# master.net
KiCad netlist of a schematic drawn in EAGLE
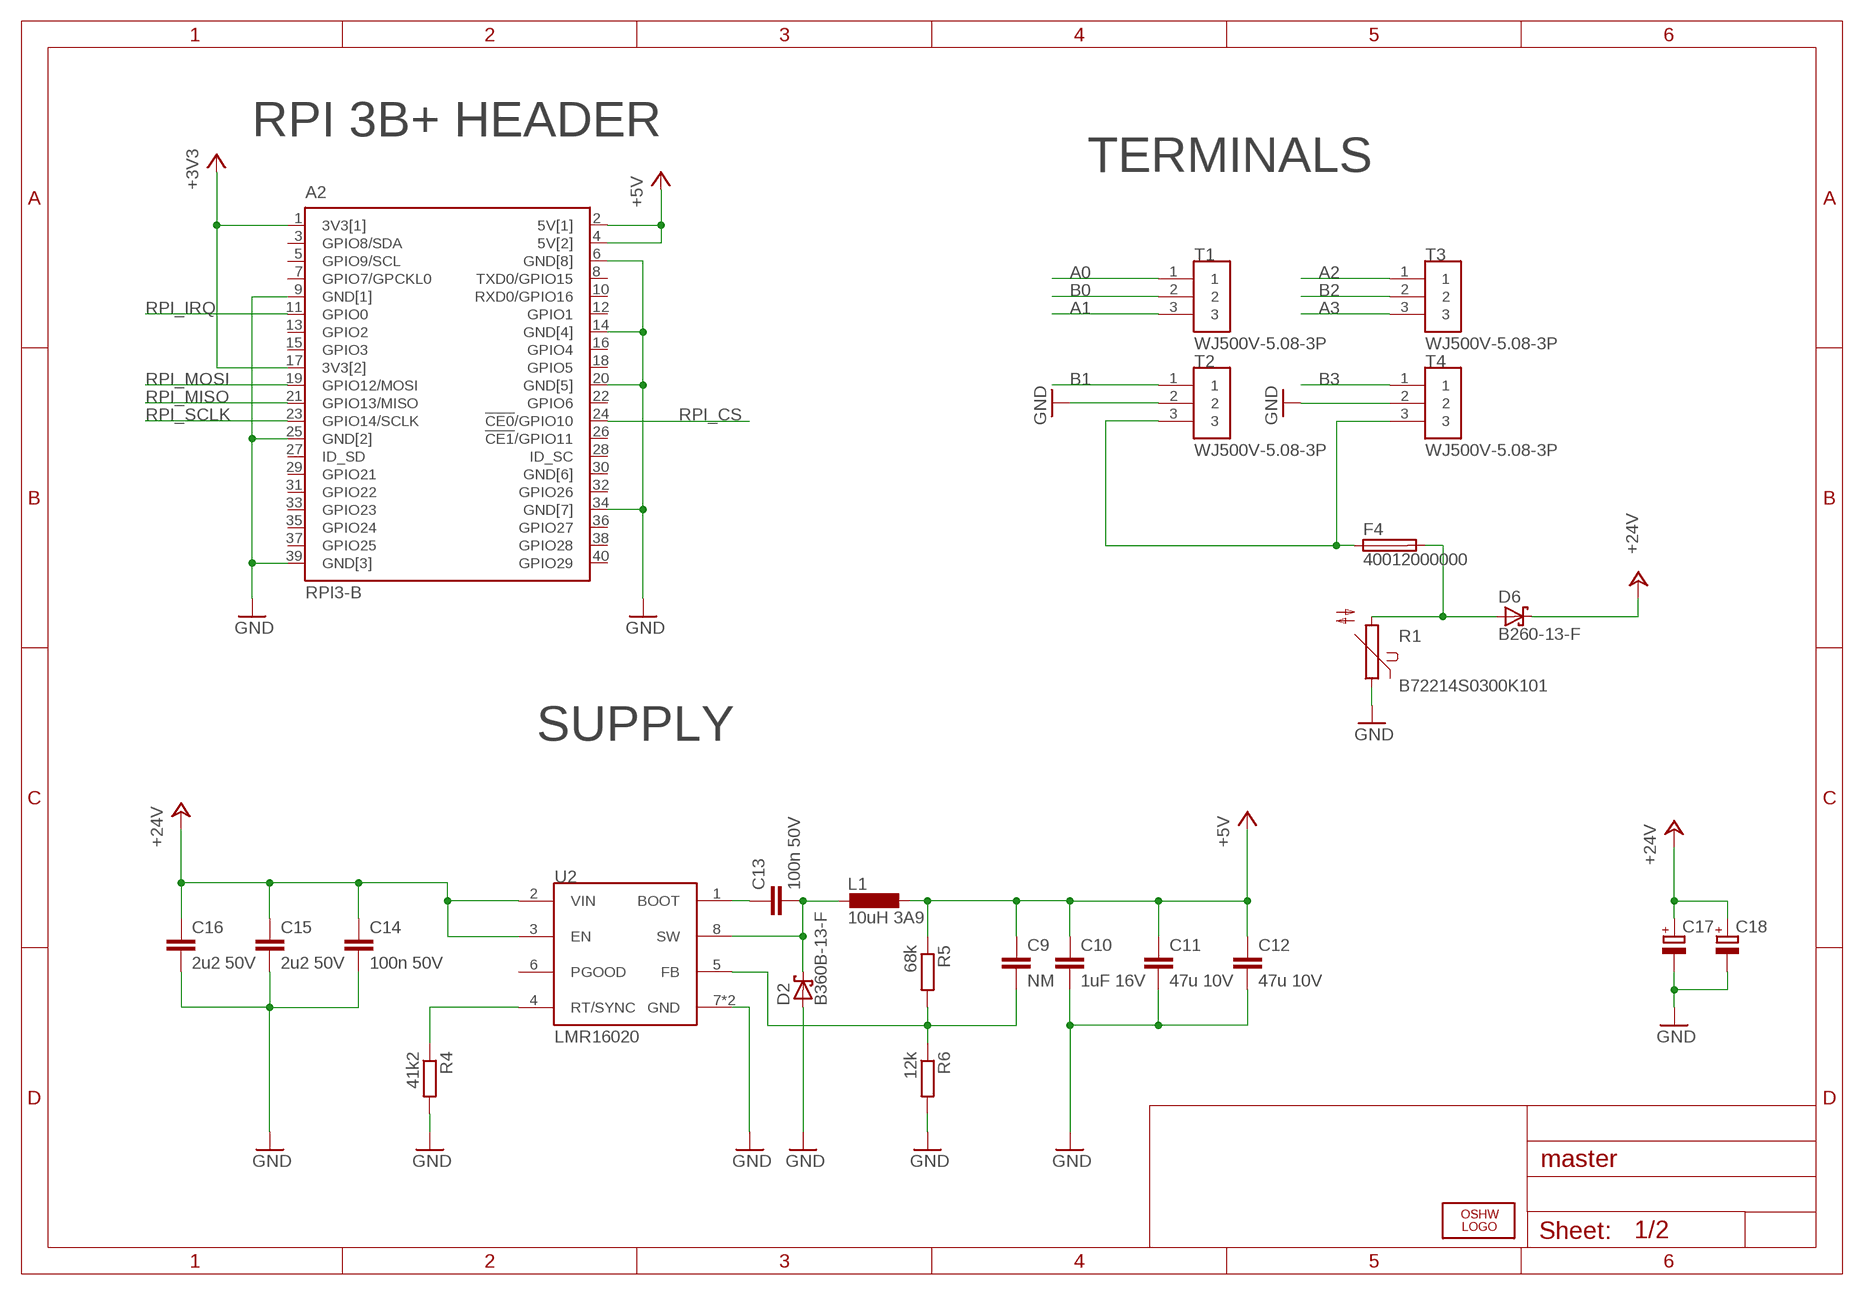
[diagram p0: schematic, sheet 1]
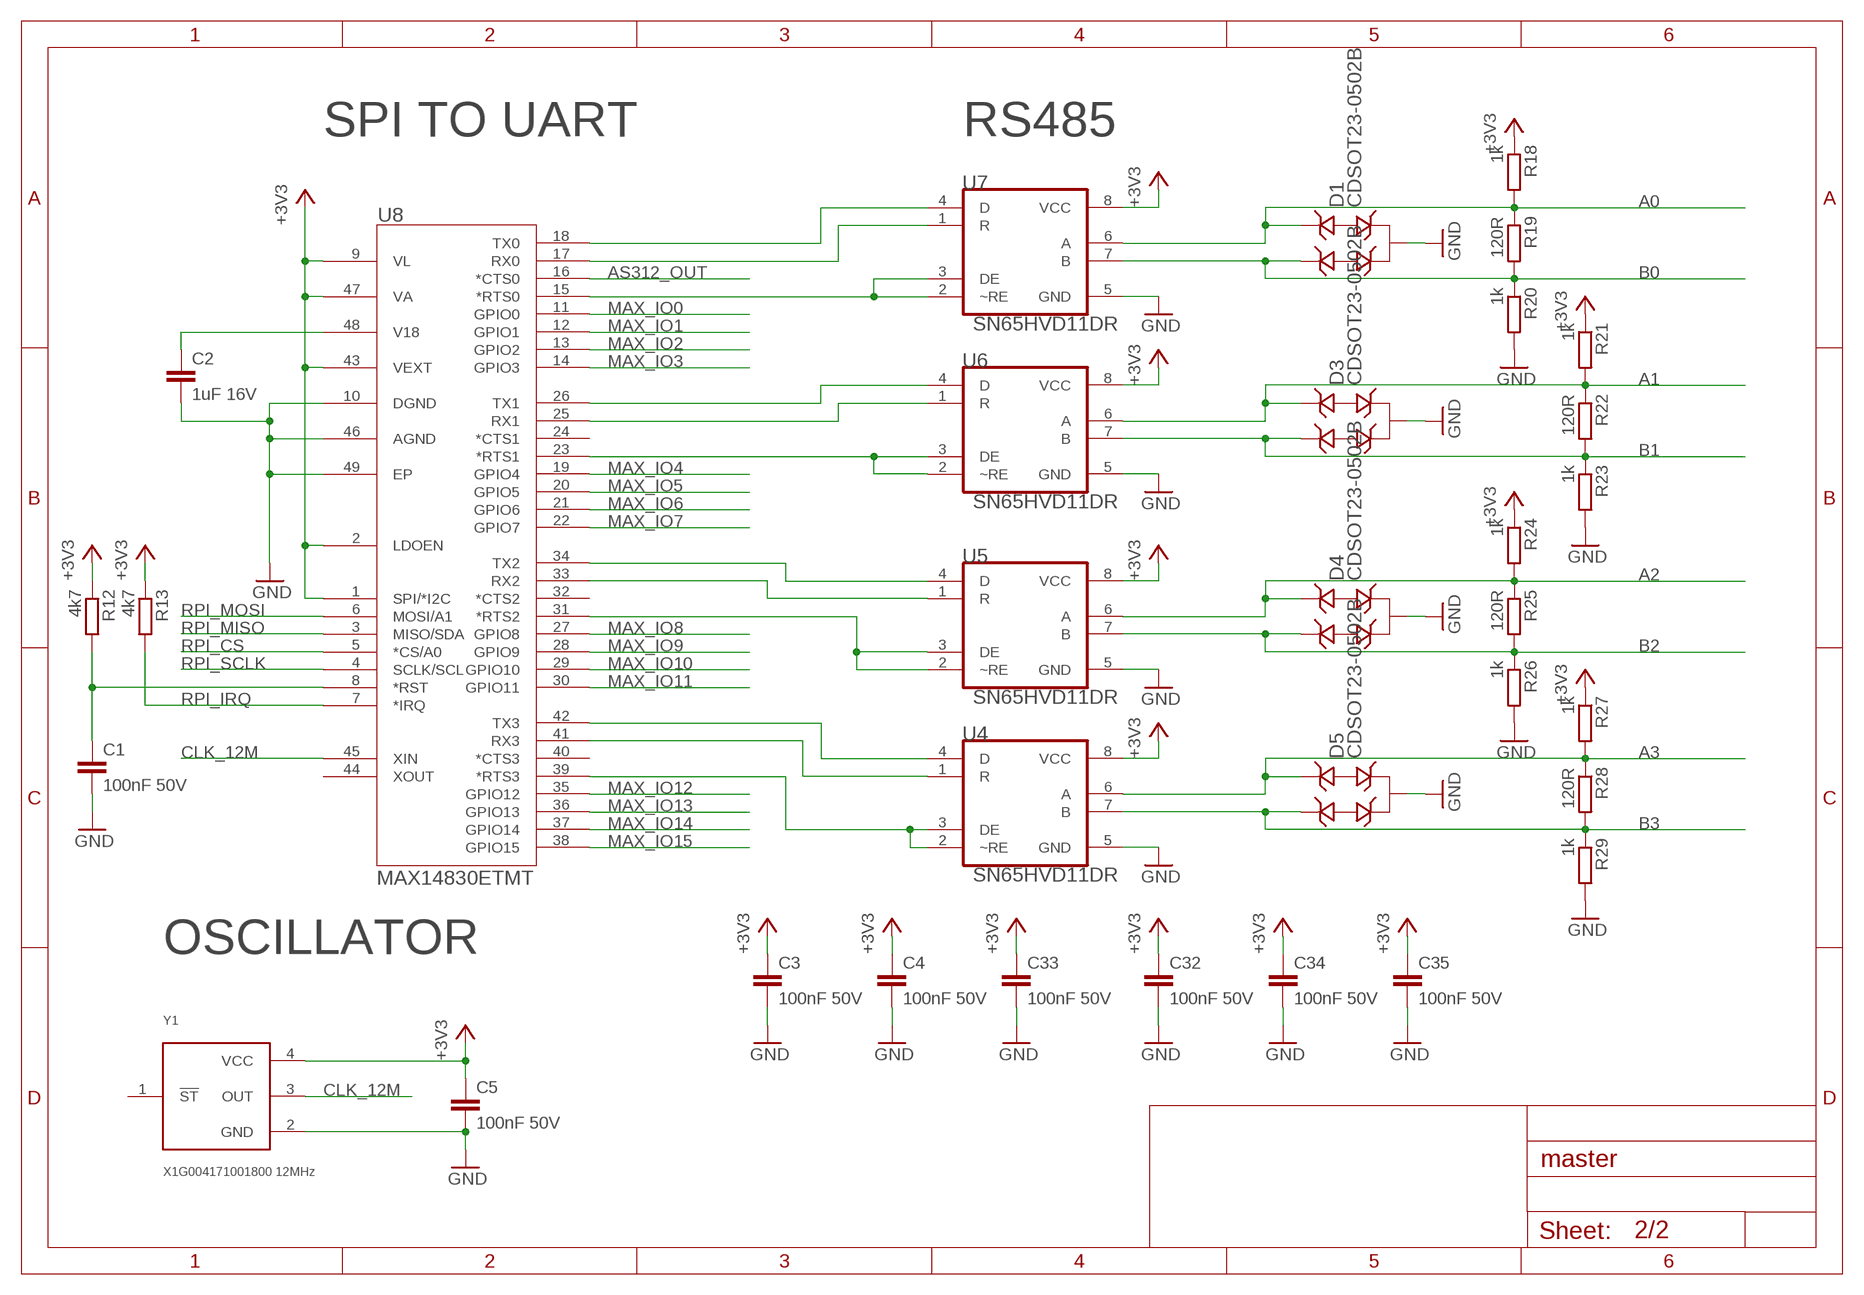
[diagram p1: schematic, sheet 2]

(export (version "E")
  (design (tool "Eeschema 10.0.6"))
  (components
    (comp (ref "C1")
      (value "100nF 50V")
      (footprint "eagle-import:C0805")
      (libsource (lib "eagle-import") (part "C-EUC0805"))
    )
    (comp (ref "C2")
      (value "1uF 16V")
      (footprint "eagle-import:C0805")
      (libsource (lib "eagle-import") (part "C-EUC0805"))
    )
    (comp (ref "C3")
      (value "100nF 50V")
      (footprint "eagle-import:C0805")
      (libsource (lib "eagle-import") (part "C-EUC0805"))
    )
    (comp (ref "C4")
      (value "100nF 50V")
      (footprint "eagle-import:C0805")
      (libsource (lib "eagle-import") (part "C-EUC0805"))
    )
    (comp (ref "C5")
      (value "100nF 50V")
      (footprint "eagle-import:C0805")
      (libsource (lib "eagle-import") (part "C-EUC0805"))
    )
    (comp (ref "C32")
      (value "100nF 50V")
      (footprint "eagle-import:C0805")
      (libsource (lib "eagle-import") (part "C-EUC0805"))
    )
    (comp (ref "C33")
      (value "100nF 50V")
      (footprint "eagle-import:C0805")
      (libsource (lib "eagle-import") (part "C-EUC0805"))
    )
    (comp (ref "C34")
      (value "100nF 50V")
      (footprint "eagle-import:C0805")
      (libsource (lib "eagle-import") (part "C-EUC0805"))
    )
    (comp (ref "C35")
      (value "100nF 50V")
      (footprint "eagle-import:C0805")
      (libsource (lib "eagle-import") (part "C-EUC0805"))
    )
    (comp (ref "D1")
      (value "CDSOT23-0502B")
      (footprint "eagle-import:SOT-23-3")
      (fields (field (name "MF") "Bourns") (field (name "MP") "CDSOT23-SM712"))
      (libsource (lib "eagle-import") (part "CDSOT23-SM712"))
    )
    (comp (ref "D3")
      (value "CDSOT23-0502B")
      (footprint "eagle-import:SOT-23-3")
      (fields (field (name "MF") "Bourns") (field (name "MP") "CDSOT23-SM712"))
      (libsource (lib "eagle-import") (part "CDSOT23-SM712"))
    )
    (comp (ref "D4")
      (value "CDSOT23-0502B")
      (footprint "eagle-import:SOT-23-3")
      (fields (field (name "MF") "Bourns") (field (name "MP") "CDSOT23-SM712"))
      (libsource (lib "eagle-import") (part "CDSOT23-SM712"))
    )
    (comp (ref "D5")
      (value "CDSOT23-0502B")
      (footprint "eagle-import:SOT-23-3")
      (fields (field (name "MF") "Bourns") (field (name "MP") "CDSOT23-SM712"))
      (libsource (lib "eagle-import") (part "CDSOT23-SM712"))
    )
    (comp (ref "R12")
      (value "4k7")
      (footprint "eagle-import:R1206")
      (libsource (lib "eagle-import") (part "R-EU_R1206"))
    )
    (comp (ref "R13")
      (value "4k7")
      (footprint "eagle-import:R1206")
      (libsource (lib "eagle-import") (part "R-EU_R1206"))
    )
    (comp (ref "R18")
      (value "1k")
      (footprint "eagle-import:R1206")
      (libsource (lib "eagle-import") (part "R-EU_R1206"))
    )
    (comp (ref "R19")
      (value "120R")
      (footprint "eagle-import:R1206")
      (libsource (lib "eagle-import") (part "R-EU_R1206"))
    )
    (comp (ref "R20")
      (value "1k")
      (footprint "eagle-import:R1206")
      (libsource (lib "eagle-import") (part "R-EU_R1206"))
    )
    (comp (ref "R21")
      (value "1k")
      (footprint "eagle-import:R1206")
      (libsource (lib "eagle-import") (part "R-EU_R1206"))
    )
    (comp (ref "R22")
      (value "120R")
      (footprint "eagle-import:R1206")
      (libsource (lib "eagle-import") (part "R-EU_R1206"))
    )
    (comp (ref "R23")
      (value "1k")
      (footprint "eagle-import:R1206")
      (libsource (lib "eagle-import") (part "R-EU_R1206"))
    )
    (comp (ref "R24")
      (value "1k")
      (footprint "eagle-import:R1206")
      (libsource (lib "eagle-import") (part "R-EU_R1206"))
    )
    (comp (ref "R25")
      (value "120R")
      (footprint "eagle-import:R1206")
      (libsource (lib "eagle-import") (part "R-EU_R1206"))
    )
    (comp (ref "R26")
      (value "1k")
      (footprint "eagle-import:R1206")
      (libsource (lib "eagle-import") (part "R-EU_R1206"))
    )
    (comp (ref "R27")
      (value "1k")
      (footprint "eagle-import:R1206")
      (libsource (lib "eagle-import") (part "R-EU_R1206"))
    )
    (comp (ref "R28")
      (value "120R")
      (footprint "eagle-import:R1206")
      (libsource (lib "eagle-import") (part "R-EU_R1206"))
    )
    (comp (ref "R29")
      (value "1k")
      (footprint "eagle-import:R1206")
      (libsource (lib "eagle-import") (part "R-EU_R1206"))
    )
    (comp (ref "U4")
      (value "SN65HVD11DR")
      (footprint "eagle-import:SOIC127P600X175-8N")
      (fields (field (name "MF") "Texas Instruments"))
      (libsource (lib "eagle-import") (part "SN65HVD11DR"))
    )
    (comp (ref "U5")
      (value "SN65HVD11DR")
      (footprint "eagle-import:SOIC127P600X175-8N")
      (fields (field (name "MF") "Texas Instruments"))
      (libsource (lib "eagle-import") (part "SN65HVD11DR"))
    )
    (comp (ref "U6")
      (value "SN65HVD11DR")
      (footprint "eagle-import:SOIC127P600X175-8N")
      (fields (field (name "MF") "Texas Instruments"))
      (libsource (lib "eagle-import") (part "SN65HVD11DR"))
    )
    (comp (ref "U7")
      (value "SN65HVD11DR")
      (footprint "eagle-import:SOIC127P600X175-8N")
      (fields (field (name "MF") "Texas Instruments"))
      (libsource (lib "eagle-import") (part "SN65HVD11DR"))
    )
    (comp (ref "U8")
      (value "MAX14830ETMT")
      (footprint "eagle-import:21-0144H_T4877-3")
      (fields (field (name "MF") "Maxim Integrated") (field (name "MP") "MAX14830ETM+"))
      (libsource (lib "eagle-import") (part "MAX14830ETMT"))
    )
    (comp (ref "Y1")
      (value "X1G004171001800 12MHz")
      (footprint "eagle-import:OSCCC250X200X80-4N")
      (fields (field (name "MF") "EPSON") (field (name "MP") "X1G0041710033"))
      (libsource (lib "eagle-import") (part "X1G0041710033"))
    )
    (comp (ref "A2")
      (value "RPI3-B")
      (footprint "eagle-import:RPI3-B")
      (fields (field (name "MF") "Raspberry Pi") (field (name "MP") "ADA3708"))
      (libsource (lib "eagle-import") (part "RPI3-B"))
    )
    (comp (ref "C9")
      (value "NM")
      (footprint "eagle-import:C0805")
      (libsource (lib "eagle-import") (part "C-EUC0805"))
    )
    (comp (ref "C10")
      (value "1uF 16V")
      (footprint "eagle-import:C0805")
      (libsource (lib "eagle-import") (part "C-EUC0805"))
    )
    (comp (ref "C11")
      (value "47u 10V")
      (footprint "eagle-import:C1210")
      (libsource (lib "eagle-import") (part "C-EUC1210"))
    )
    (comp (ref "C12")
      (value "47u 10V")
      (footprint "eagle-import:C1210")
      (libsource (lib "eagle-import") (part "C-EUC1210"))
    )
    (comp (ref "C13")
      (value "100n 50V")
      (footprint "eagle-import:C1206")
      (libsource (lib "eagle-import") (part "C-EUC1206"))
    )
    (comp (ref "C14")
      (value "100n 50V")
      (footprint "eagle-import:C1206")
      (libsource (lib "eagle-import") (part "C-EUC1206"))
    )
    (comp (ref "C15")
      (value "2u2 50V")
      (footprint "eagle-import:C1206")
      (libsource (lib "eagle-import") (part "C-EUC1206"))
    )
    (comp (ref "C16")
      (value "2u2 50V")
      (footprint "eagle-import:C1206")
      (libsource (lib "eagle-import") (part "C-EUC1206"))
    )
    (comp (ref "C17")
      (value "CPOL-EUUD-5X5,8")
      (footprint "eagle-import:UD-5X5,8_NICHICON")
      (libsource (lib "eagle-import") (part "CPOL-EUUD-5X5,8"))
    )
    (comp (ref "C18")
      (value "CPOL-EUUD-5X5,8")
      (footprint "eagle-import:UD-5X5,8_NICHICON")
      (libsource (lib "eagle-import") (part "CPOL-EUUD-5X5,8"))
    )
    (comp (ref "D2")
      (value "B360B-13-F")
      (footprint "eagle-import:SMB")
      (libsource (lib "eagle-import") (part "MBRS130LT3"))
    )
    (comp (ref "D6")
      (value "B260-13-F")
      (footprint "eagle-import:SMB")
      (libsource (lib "eagle-import") (part "MBRS130LT3"))
    )
    (comp (ref "F4")
      (value "40012000000")
      (footprint "eagle-import:400")
      (libsource (lib "eagle-import") (part "40012000000"))
    )
    (comp (ref "L1")
      (value "10uH 3A9")
      (footprint "eagle-import:1217AS")
      (libsource (lib "eagle-import") (part "1217AS-H-100M=P3"))
    )
    (comp (ref "LOGO1")
      (value "OSHW_LOGO_FILLX0350-NT")
      (footprint "eagle-import:OSHW_FILLX350_NOTEXT")
      (libsource (lib "eagle-import") (part "OSHW_LOGO_FILLX0350-NT"))
    )
    (comp (ref "R1")
      (value "B72214S0300K101")
      (footprint "eagle-import:S14K300")
      (libsource (lib "eagle-import") (part "S14K300"))
    )
    (comp (ref "R4")
      (value "41k2")
      (footprint "eagle-import:R1206")
      (libsource (lib "eagle-import") (part "R-EU_R1206"))
    )
    (comp (ref "R5")
      (value "68k")
      (footprint "eagle-import:R1206")
      (libsource (lib "eagle-import") (part "R-EU_R1206"))
    )
    (comp (ref "R6")
      (value "12k")
      (footprint "eagle-import:R1206")
      (libsource (lib "eagle-import") (part "R-EU_R1206"))
    )
    (comp (ref "T1")
      (value "WJ500V-5.08-3P")
      (footprint "eagle-import:WJ500V-5.08-3P")
      (libsource (lib "eagle-import") (part "WJ500V-5.08-3P"))
    )
    (comp (ref "T2")
      (value "WJ500V-5.08-3P")
      (footprint "eagle-import:WJ500V-5.08-3P")
      (libsource (lib "eagle-import") (part "WJ500V-5.08-3P"))
    )
    (comp (ref "T3")
      (value "WJ500V-5.08-3P")
      (footprint "eagle-import:WJ500V-5.08-3P")
      (libsource (lib "eagle-import") (part "WJ500V-5.08-3P"))
    )
    (comp (ref "T4")
      (value "WJ500V-5.08-3P")
      (footprint "eagle-import:WJ500V-5.08-3P")
      (libsource (lib "eagle-import") (part "WJ500V-5.08-3P"))
    )
    (comp (ref "U2")
      (value "LMR16020")
      (footprint "eagle-import:SOIC127P600X170-8N")
      (libsource (lib "eagle-import") (part "LMR16020"))
    )
  )
  (nets
    (net (code "1") (name "+3V3") (class "Default")
      (node (ref "A2") (pin "1") (pinfunction "3V3[1]_1") (pintype "power_in"))
      (node (ref "A2") (pin "17") (pinfunction "3V3[2]_17") (pintype "power_in"))
      (node (ref "C3") (pin "1") (pinfunction "1_1") (pintype "passive"))
      (node (ref "C32") (pin "1") (pinfunction "1_1") (pintype "passive"))
      (node (ref "C33") (pin "1") (pinfunction "1_1") (pintype "passive"))
      (node (ref "C34") (pin "1") (pinfunction "1_1") (pintype "passive"))
      (node (ref "C35") (pin "1") (pinfunction "1_1") (pintype "passive"))
      (node (ref "C4") (pin "1") (pinfunction "1_1") (pintype "passive"))
      (node (ref "C5") (pin "1") (pinfunction "1_1") (pintype "passive"))
      (node (ref "R12") (pin "1") (pinfunction "1_1") (pintype "passive"))
      (node (ref "R13") (pin "1") (pinfunction "1_1") (pintype "passive"))
      (node (ref "R18") (pin "1") (pinfunction "1_1") (pintype "passive"))
      (node (ref "R21") (pin "1") (pinfunction "1_1") (pintype "passive"))
      (node (ref "R24") (pin "1") (pinfunction "1_1") (pintype "passive"))
      (node (ref "R27") (pin "1") (pinfunction "1_1") (pintype "passive"))
      (node (ref "U4") (pin "8") (pinfunction "VCC_8") (pintype "power_in"))
      (node (ref "U5") (pin "8") (pinfunction "VCC_8") (pintype "power_in"))
      (node (ref "U6") (pin "8") (pinfunction "VCC_8") (pintype "power_in"))
      (node (ref "U7") (pin "8") (pinfunction "VCC_8") (pintype "power_in"))
      (node (ref "U8") (pin "1") (pinfunction "SPI/*I2C_1") (pintype "passive"))
      (node (ref "U8") (pin "2") (pinfunction "LDOEN_2") (pintype "passive"))
      (node (ref "U8") (pin "43") (pinfunction "VEXT_43") (pintype "passive"))
      (node (ref "U8") (pin "47") (pinfunction "VA_47") (pintype "passive"))
      (node (ref "U8") (pin "9") (pinfunction "VL_9") (pintype "power_in"))
      (node (ref "Y1") (pin "4") (pinfunction "VCC_4") (pintype "power_in"))
    )
    (net (code "2") (name "+5V") (class "Default")
      (node (ref "A2") (pin "2") (pinfunction "5V[1]_2") (pintype "power_in"))
      (node (ref "A2") (pin "4") (pinfunction "5V[2]_4") (pintype "power_in"))
      (node (ref "C10") (pin "1") (pinfunction "1_1") (pintype "passive"))
      (node (ref "C11") (pin "1") (pinfunction "1_1") (pintype "passive"))
      (node (ref "C12") (pin "1") (pinfunction "1_1") (pintype "passive"))
      (node (ref "C9") (pin "1") (pinfunction "1_1") (pintype "passive"))
      (node (ref "L1") (pin "1") (pinfunction "1_1") (pintype "passive"))
      (node (ref "R5") (pin "1") (pinfunction "1_1") (pintype "passive"))
    )
    (net (code "3") (name "+24V") (class "Default")
      (node (ref "C14") (pin "1") (pinfunction "1_1") (pintype "passive"))
      (node (ref "C15") (pin "1") (pinfunction "1_1") (pintype "passive"))
      (node (ref "C16") (pin "1") (pinfunction "1_1") (pintype "passive"))
      (node (ref "C17") (pin "+") (pinfunction "+_+") (pintype "passive"))
      (node (ref "C18") (pin "+") (pinfunction "+_+") (pintype "passive"))
      (node (ref "D6") (pin "C") (pinfunction "C_C") (pintype "passive"))
      (node (ref "U2") (pin "2") (pinfunction "VIN_2") (pintype "power_in"))
      (node (ref "U2") (pin "3") (pinfunction "EN_3") (pintype "input"))
    )
    (net (code "4") (name "A0") (class "Default")
      (node (ref "D1") (pin "2") (pinfunction "IO2_2") (pintype "bidirectional"))
      (node (ref "R18") (pin "2") (pinfunction "2_2") (pintype "passive"))
      (node (ref "R19") (pin "1") (pinfunction "1_1") (pintype "passive"))
      (node (ref "T1") (pin "1") (pinfunction "1_1") (pintype "passive"))
      (node (ref "U7") (pin "6") (pinfunction "A_6") (pintype "output"))
    )
    (net (code "5") (name "A1") (class "Default")
      (node (ref "D3") (pin "2") (pinfunction "IO2_2") (pintype "bidirectional"))
      (node (ref "R21") (pin "2") (pinfunction "2_2") (pintype "passive"))
      (node (ref "R22") (pin "1") (pinfunction "1_1") (pintype "passive"))
      (node (ref "T1") (pin "3") (pinfunction "3_3") (pintype "passive"))
      (node (ref "U6") (pin "6") (pinfunction "A_6") (pintype "output"))
    )
    (net (code "6") (name "A2") (class "Default")
      (node (ref "D4") (pin "2") (pinfunction "IO2_2") (pintype "bidirectional"))
      (node (ref "R24") (pin "2") (pinfunction "2_2") (pintype "passive"))
      (node (ref "R25") (pin "1") (pinfunction "1_1") (pintype "passive"))
      (node (ref "T3") (pin "1") (pinfunction "1_1") (pintype "passive"))
      (node (ref "U5") (pin "6") (pinfunction "A_6") (pintype "output"))
    )
    (net (code "7") (name "A3") (class "Default")
      (node (ref "D5") (pin "2") (pinfunction "IO2_2") (pintype "bidirectional"))
      (node (ref "R27") (pin "2") (pinfunction "2_2") (pintype "passive"))
      (node (ref "R28") (pin "1") (pinfunction "1_1") (pintype "passive"))
      (node (ref "T3") (pin "3") (pinfunction "3_3") (pintype "passive"))
      (node (ref "U4") (pin "6") (pinfunction "A_6") (pintype "output"))
    )
    (net (code "8") (name "AS312_OUT") (class "Default")
      (node (ref "U8") (pin "16") (pinfunction "*CTS0_16") (pintype "passive"))
    )
    (net (code "9") (name "B0") (class "Default")
      (node (ref "D1") (pin "1") (pinfunction "IO1_1") (pintype "bidirectional"))
      (node (ref "R19") (pin "2") (pinfunction "2_2") (pintype "passive"))
      (node (ref "R20") (pin "1") (pinfunction "1_1") (pintype "passive"))
      (node (ref "T1") (pin "2") (pinfunction "2_2") (pintype "passive"))
      (node (ref "U7") (pin "7") (pinfunction "B_7") (pintype "output"))
    )
    (net (code "10") (name "B1") (class "Default")
      (node (ref "D3") (pin "1") (pinfunction "IO1_1") (pintype "bidirectional"))
      (node (ref "R22") (pin "2") (pinfunction "2_2") (pintype "passive"))
      (node (ref "R23") (pin "1") (pinfunction "1_1") (pintype "passive"))
      (node (ref "T2") (pin "1") (pinfunction "1_1") (pintype "passive"))
      (node (ref "U6") (pin "7") (pinfunction "B_7") (pintype "output"))
    )
    (net (code "11") (name "B2") (class "Default")
      (node (ref "D4") (pin "1") (pinfunction "IO1_1") (pintype "bidirectional"))
      (node (ref "R25") (pin "2") (pinfunction "2_2") (pintype "passive"))
      (node (ref "R26") (pin "1") (pinfunction "1_1") (pintype "passive"))
      (node (ref "T3") (pin "2") (pinfunction "2_2") (pintype "passive"))
      (node (ref "U5") (pin "7") (pinfunction "B_7") (pintype "output"))
    )
    (net (code "12") (name "B3") (class "Default")
      (node (ref "D5") (pin "1") (pinfunction "IO1_1") (pintype "bidirectional"))
      (node (ref "R28") (pin "2") (pinfunction "2_2") (pintype "passive"))
      (node (ref "R29") (pin "1") (pinfunction "1_1") (pintype "passive"))
      (node (ref "T4") (pin "1") (pinfunction "1_1") (pintype "passive"))
      (node (ref "U4") (pin "7") (pinfunction "B_7") (pintype "output"))
    )
    (net (code "13") (name "CLK_12M") (class "Default")
      (node (ref "U8") (pin "45") (pinfunction "XIN_45") (pintype "passive"))
      (node (ref "Y1") (pin "3") (pinfunction "OUT_3") (pintype "output"))
    )
    (net (code "14") (name "GND") (class "Default")
      (node (ref "A2") (pin "14") (pinfunction "GND[4]_14") (pintype "power_in"))
      (node (ref "A2") (pin "20") (pinfunction "GND[5]_20") (pintype "power_in"))
      (node (ref "A2") (pin "25") (pinfunction "GND[2]_25") (pintype "power_in"))
      (node (ref "A2") (pin "34") (pinfunction "GND[7]_34") (pintype "power_in"))
      (node (ref "A2") (pin "39") (pinfunction "GND[3]_39") (pintype "power_in"))
      (node (ref "A2") (pin "6") (pinfunction "GND[8]_6") (pintype "power_in"))
      (node (ref "A2") (pin "9") (pinfunction "GND[1]_9") (pintype "power_in"))
      (node (ref "C1") (pin "2") (pinfunction "2_2") (pintype "passive"))
      (node (ref "C10") (pin "2") (pinfunction "2_2") (pintype "passive"))
      (node (ref "C11") (pin "2") (pinfunction "2_2") (pintype "passive"))
      (node (ref "C12") (pin "2") (pinfunction "2_2") (pintype "passive"))
      (node (ref "C14") (pin "2") (pinfunction "2_2") (pintype "passive"))
      (node (ref "C15") (pin "2") (pinfunction "2_2") (pintype "passive"))
      (node (ref "C16") (pin "2") (pinfunction "2_2") (pintype "passive"))
      (node (ref "C17") (pin "-") (pinfunction "-_-") (pintype "passive"))
      (node (ref "C18") (pin "-") (pinfunction "-_-") (pintype "passive"))
      (node (ref "C2") (pin "2") (pinfunction "2_2") (pintype "passive"))
      (node (ref "C3") (pin "2") (pinfunction "2_2") (pintype "passive"))
      (node (ref "C32") (pin "2") (pinfunction "2_2") (pintype "passive"))
      (node (ref "C33") (pin "2") (pinfunction "2_2") (pintype "passive"))
      (node (ref "C34") (pin "2") (pinfunction "2_2") (pintype "passive"))
      (node (ref "C35") (pin "2") (pinfunction "2_2") (pintype "passive"))
      (node (ref "C4") (pin "2") (pinfunction "2_2") (pintype "passive"))
      (node (ref "C5") (pin "2") (pinfunction "2_2") (pintype "passive"))
      (node (ref "D1") (pin "3") (pinfunction "GND_3") (pintype "bidirectional"))
      (node (ref "D2") (pin "A") (pinfunction "A_A") (pintype "passive"))
      (node (ref "D3") (pin "3") (pinfunction "GND_3") (pintype "bidirectional"))
      (node (ref "D4") (pin "3") (pinfunction "GND_3") (pintype "bidirectional"))
      (node (ref "D5") (pin "3") (pinfunction "GND_3") (pintype "bidirectional"))
      (node (ref "R1") (pin "1") (pinfunction "1_1") (pintype "passive"))
      (node (ref "R20") (pin "2") (pinfunction "2_2") (pintype "passive"))
      (node (ref "R23") (pin "2") (pinfunction "2_2") (pintype "passive"))
      (node (ref "R26") (pin "2") (pinfunction "2_2") (pintype "passive"))
      (node (ref "R29") (pin "2") (pinfunction "2_2") (pintype "passive"))
      (node (ref "R4") (pin "2") (pinfunction "2_2") (pintype "passive"))
      (node (ref "R6") (pin "2") (pinfunction "2_2") (pintype "passive"))
      (node (ref "T2") (pin "2") (pinfunction "2_2") (pintype "passive"))
      (node (ref "T4") (pin "2") (pinfunction "2_2") (pintype "passive"))
      (node (ref "U2") (pin "7") (pinfunction "GND_7") (pintype "power_in"))
      (node (ref "U2") (pin "9") (pinfunction "GND_9") (pintype "power_in"))
      (node (ref "U4") (pin "5") (pinfunction "GND_5") (pintype "passive"))
      (node (ref "U5") (pin "5") (pinfunction "GND_5") (pintype "passive"))
      (node (ref "U6") (pin "5") (pinfunction "GND_5") (pintype "passive"))
      (node (ref "U7") (pin "5") (pinfunction "GND_5") (pintype "passive"))
      (node (ref "U8") (pin "10") (pinfunction "DGND_10") (pintype "power_in"))
      (node (ref "U8") (pin "46") (pinfunction "AGND_46") (pintype "power_in"))
      (node (ref "U8") (pin "49") (pinfunction "EP_49") (pintype "passive"))
      (node (ref "Y1") (pin "2") (pinfunction "GND_2") (pintype "passive"))
    )
    (net (code "15") (name "GND[6]") (class "Default")
      (node (ref "A2") (pin "30") (pinfunction "GND[6]_30") (pintype "power_in"))
    )
    (net (code "16") (name "MAX_IO0") (class "Default")
      (node (ref "U8") (pin "11") (pinfunction "GPIO0_11") (pintype "passive"))
    )
    (net (code "17") (name "MAX_IO1") (class "Default")
      (node (ref "U8") (pin "12") (pinfunction "GPIO1_12") (pintype "passive"))
    )
    (net (code "18") (name "MAX_IO2") (class "Default")
      (node (ref "U8") (pin "13") (pinfunction "GPIO2_13") (pintype "passive"))
    )
    (net (code "19") (name "MAX_IO3") (class "Default")
      (node (ref "U8") (pin "14") (pinfunction "GPIO3_14") (pintype "passive"))
    )
    (net (code "20") (name "MAX_IO4") (class "Default")
      (node (ref "U8") (pin "19") (pinfunction "GPIO4_19") (pintype "passive"))
    )
    (net (code "21") (name "MAX_IO5") (class "Default")
      (node (ref "U8") (pin "20") (pinfunction "GPIO5_20") (pintype "passive"))
    )
    (net (code "22") (name "MAX_IO6") (class "Default")
      (node (ref "U8") (pin "21") (pinfunction "GPIO6_21") (pintype "passive"))
    )
    (net (code "23") (name "MAX_IO7") (class "Default")
      (node (ref "U8") (pin "22") (pinfunction "GPIO7_22") (pintype "passive"))
    )
    (net (code "24") (name "MAX_IO8") (class "Default")
      (node (ref "U8") (pin "27") (pinfunction "GPIO8_27") (pintype "passive"))
    )
    (net (code "25") (name "MAX_IO9") (class "Default")
      (node (ref "U8") (pin "28") (pinfunction "GPIO9_28") (pintype "passive"))
    )
    (net (code "26") (name "MAX_IO10") (class "Default")
      (node (ref "U8") (pin "29") (pinfunction "GPIO10_29") (pintype "passive"))
    )
    (net (code "27") (name "MAX_IO11") (class "Default")
      (node (ref "U8") (pin "30") (pinfunction "GPIO11_30") (pintype "passive"))
    )
    (net (code "28") (name "MAX_IO12") (class "Default")
      (node (ref "U8") (pin "35") (pinfunction "GPIO12_35") (pintype "passive"))
    )
    (net (code "29") (name "MAX_IO13") (class "Default")
      (node (ref "U8") (pin "36") (pinfunction "GPIO13_36") (pintype "passive"))
    )
    (net (code "30") (name "MAX_IO14") (class "Default")
      (node (ref "U8") (pin "37") (pinfunction "GPIO14_37") (pintype "passive"))
    )
    (net (code "31") (name "MAX_IO15") (class "Default")
      (node (ref "U8") (pin "38") (pinfunction "GPIO15_38") (pintype "passive"))
    )
    (net (code "32") (name "Net-(F4-1)") (class "Default")
      (node (ref "F4") (pin "P$1") (pinfunction "1_P$1") (pintype "passive"))
      (node (ref "T2") (pin "3") (pinfunction "3_3") (pintype "passive"))
      (node (ref "T4") (pin "3") (pinfunction "3_3") (pintype "passive"))
    )
    (net (code "33") (name "Net-(F4-2)") (class "Default")
      (node (ref "D6") (pin "A") (pinfunction "A_A") (pintype "passive"))
      (node (ref "F4") (pin "P$2") (pinfunction "2_P$2") (pintype "passive"))
      (node (ref "R1") (pin "2") (pinfunction "2_2") (pintype "passive"))
    )
    (net (code "34") (name "Net-(U2-BOOT)") (class "Default")
      (node (ref "C13") (pin "1") (pinfunction "1_1") (pintype "passive"))
      (node (ref "U2") (pin "1") (pinfunction "BOOT_1") (pintype "power_in"))
    )
    (net (code "35") (name "Net-(U2-FB)") (class "Default")
      (node (ref "C9") (pin "2") (pinfunction "2_2") (pintype "passive"))
      (node (ref "R5") (pin "2") (pinfunction "2_2") (pintype "passive"))
      (node (ref "R6") (pin "1") (pinfunction "1_1") (pintype "passive"))
      (node (ref "U2") (pin "5") (pinfunction "FB_5") (pintype "input"))
    )
    (net (code "36") (name "Net-(U2-RT{slash}SYNC)") (class "Default")
      (node (ref "R4") (pin "1") (pinfunction "1_1") (pintype "passive"))
      (node (ref "U2") (pin "4") (pinfunction "RT/SYNC_4") (pintype "input"))
    )
    (net (code "37") (name "Net-(U2-SW)") (class "Default")
      (node (ref "C13") (pin "2") (pinfunction "2_2") (pintype "passive"))
      (node (ref "D2") (pin "C") (pinfunction "C_C") (pintype "passive"))
      (node (ref "L1") (pin "2") (pinfunction "2_2") (pintype "passive"))
      (node (ref "U2") (pin "8") (pinfunction "SW_8") (pintype "output"))
    )
    (net (code "38") (name "Net-(U4-D)") (class "Default")
      (node (ref "U4") (pin "4") (pinfunction "D_4") (pintype "input"))
      (node (ref "U8") (pin "42") (pinfunction "TX3_42") (pintype "passive"))
    )
    (net (code "39") (name "Net-(U4-DE)") (class "Default")
      (node (ref "U4") (pin "2") (pinfunction "~{RE}_2") (pintype "input"))
      (node (ref "U4") (pin "3") (pinfunction "DE_3") (pintype "input"))
      (node (ref "U8") (pin "39") (pinfunction "*RTS3_39") (pintype "passive"))
    )
    (net (code "40") (name "Net-(U4-R)") (class "Default")
      (node (ref "U4") (pin "1") (pinfunction "R_1") (pintype "output"))
      (node (ref "U8") (pin "41") (pinfunction "RX3_41") (pintype "passive"))
    )
    (net (code "41") (name "Net-(U5-D)") (class "Default")
      (node (ref "U5") (pin "4") (pinfunction "D_4") (pintype "input"))
      (node (ref "U8") (pin "34") (pinfunction "TX2_34") (pintype "passive"))
    )
    (net (code "42") (name "Net-(U5-DE)") (class "Default")
      (node (ref "U5") (pin "2") (pinfunction "~{RE}_2") (pintype "input"))
      (node (ref "U5") (pin "3") (pinfunction "DE_3") (pintype "input"))
      (node (ref "U8") (pin "31") (pinfunction "*RTS2_31") (pintype "passive"))
    )
    (net (code "43") (name "Net-(U5-R)") (class "Default")
      (node (ref "U5") (pin "1") (pinfunction "R_1") (pintype "output"))
      (node (ref "U8") (pin "33") (pinfunction "RX2_33") (pintype "passive"))
    )
    (net (code "44") (name "Net-(U6-D)") (class "Default")
      (node (ref "U6") (pin "4") (pinfunction "D_4") (pintype "input"))
      (node (ref "U8") (pin "26") (pinfunction "TX1_26") (pintype "passive"))
    )
    (net (code "45") (name "Net-(U6-DE)") (class "Default")
      (node (ref "U6") (pin "2") (pinfunction "~{RE}_2") (pintype "input"))
      (node (ref "U6") (pin "3") (pinfunction "DE_3") (pintype "input"))
      (node (ref "U8") (pin "23") (pinfunction "*RTS1_23") (pintype "passive"))
    )
    (net (code "46") (name "Net-(U6-R)") (class "Default")
      (node (ref "U6") (pin "1") (pinfunction "R_1") (pintype "output"))
      (node (ref "U8") (pin "25") (pinfunction "RX1_25") (pintype "passive"))
    )
    (net (code "47") (name "Net-(U7-D)") (class "Default")
      (node (ref "U7") (pin "4") (pinfunction "D_4") (pintype "input"))
      (node (ref "U8") (pin "18") (pinfunction "TX0_18") (pintype "passive"))
    )
    (net (code "48") (name "Net-(U7-DE)") (class "Default")
      (node (ref "U7") (pin "2") (pinfunction "~{RE}_2") (pintype "input"))
      (node (ref "U7") (pin "3") (pinfunction "DE_3") (pintype "input"))
      (node (ref "U8") (pin "15") (pinfunction "*RTS0_15") (pintype "passive"))
    )
    (net (code "49") (name "Net-(U7-R)") (class "Default")
      (node (ref "U7") (pin "1") (pinfunction "R_1") (pintype "output"))
      (node (ref "U8") (pin "17") (pinfunction "RX0_17") (pintype "passive"))
    )
    (net (code "50") (name "Net-(U8-*RST)") (class "Default")
      (node (ref "C1") (pin "1") (pinfunction "1_1") (pintype "passive"))
      (node (ref "R12") (pin "2") (pinfunction "2_2") (pintype "passive"))
      (node (ref "U8") (pin "8") (pinfunction "*RST_8") (pintype "passive"))
    )
    (net (code "51") (name "Net-(U8-V18)") (class "Default")
      (node (ref "C2") (pin "1") (pinfunction "1_1") (pintype "passive"))
      (node (ref "U8") (pin "48") (pinfunction "V18_48") (pintype "power_in"))
    )
    (net (code "52") (name "RPI_CS") (class "Default")
      (node (ref "A2") (pin "24") (pinfunction "~{CE0}/GPIO10_24") (pintype "bidirectional"))
      (node (ref "U8") (pin "5") (pinfunction "*CS/A0_5") (pintype "passive"))
    )
    (net (code "53") (name "RPI_IRQ") (class "Default")
      (node (ref "A2") (pin "11") (pinfunction "GPIO0_11") (pintype "bidirectional"))
      (node (ref "R13") (pin "2") (pinfunction "2_2") (pintype "passive"))
      (node (ref "U8") (pin "7") (pinfunction "*IRQ_7") (pintype "passive"))
    )
    (net (code "54") (name "RPI_MISO") (class "Default")
      (node (ref "A2") (pin "21") (pinfunction "GPIO13/MISO_21") (pintype "bidirectional"))
      (node (ref "U8") (pin "3") (pinfunction "MISO/SDA_3") (pintype "passive"))
    )
    (net (code "55") (name "RPI_MOSI") (class "Default")
      (node (ref "A2") (pin "19") (pinfunction "GPIO12/MOSI_19") (pintype "bidirectional"))
      (node (ref "U8") (pin "6") (pinfunction "MOSI/A1_6") (pintype "passive"))
    )
    (net (code "56") (name "RPI_SCLK") (class "Default")
      (node (ref "A2") (pin "23") (pinfunction "GPIO14/SCLK_23") (pintype "bidirectional"))
      (node (ref "U8") (pin "4") (pinfunction "SCLK/SCL_4") (pintype "passive"))
    )
    (net (code "57") (name "unconnected-(A2-GPIO1-Pad12)") (class "Default")
      (node (ref "A2") (pin "12") (pinfunction "GPIO1_12") (pintype "bidirectional"))
    )
    (net (code "58") (name "unconnected-(A2-GPIO2-Pad13)") (class "Default")
      (node (ref "A2") (pin "13") (pinfunction "GPIO2_13") (pintype "bidirectional"))
    )
    (net (code "59") (name "unconnected-(A2-GPIO3-Pad15)") (class "Default")
      (node (ref "A2") (pin "15") (pinfunction "GPIO3_15") (pintype "bidirectional"))
    )
    (net (code "60") (name "unconnected-(A2-GPIO4-Pad16)") (class "Default")
      (node (ref "A2") (pin "16") (pinfunction "GPIO4_16") (pintype "bidirectional"))
    )
    (net (code "61") (name "unconnected-(A2-GPIO5-Pad18)") (class "Default")
      (node (ref "A2") (pin "18") (pinfunction "GPIO5_18") (pintype "bidirectional"))
    )
    (net (code "62") (name "unconnected-(A2-GPIO6-Pad22)") (class "Default")
      (node (ref "A2") (pin "22") (pinfunction "GPIO6_22") (pintype "bidirectional"))
    )
    (net (code "63") (name "unconnected-(A2-GPIO7{slash}GPCKL0-Pad7)") (class "Default")
      (node (ref "A2") (pin "7") (pinfunction "GPIO7/GPCKL0_7") (pintype "bidirectional"))
    )
    (net (code "64") (name "unconnected-(A2-GPIO8{slash}SDA-Pad3)") (class "Default")
      (node (ref "A2") (pin "3") (pinfunction "GPIO8/SDA_3") (pintype "bidirectional"))
    )
    (net (code "65") (name "unconnected-(A2-GPIO9{slash}SCL-Pad5)") (class "Default")
      (node (ref "A2") (pin "5") (pinfunction "GPIO9/SCL_5") (pintype "bidirectional"))
    )
    (net (code "66") (name "unconnected-(A2-GPIO21-Pad29)") (class "Default")
      (node (ref "A2") (pin "29") (pinfunction "GPIO21_29") (pintype "bidirectional"))
    )
    (net (code "67") (name "unconnected-(A2-GPIO22-Pad31)") (class "Default")
      (node (ref "A2") (pin "31") (pinfunction "GPIO22_31") (pintype "bidirectional"))
    )
    (net (code "68") (name "unconnected-(A2-GPIO23-Pad33)") (class "Default")
      (node (ref "A2") (pin "33") (pinfunction "GPIO23_33") (pintype "bidirectional"))
    )
    (net (code "69") (name "unconnected-(A2-GPIO24-Pad35)") (class "Default")
      (node (ref "A2") (pin "35") (pinfunction "GPIO24_35") (pintype "bidirectional"))
    )
    (net (code "70") (name "unconnected-(A2-GPIO25-Pad37)") (class "Default")
      (node (ref "A2") (pin "37") (pinfunction "GPIO25_37") (pintype "bidirectional"))
    )
    (net (code "71") (name "unconnected-(A2-GPIO26-Pad32)") (class "Default")
      (node (ref "A2") (pin "32") (pinfunction "GPIO26_32") (pintype "bidirectional"))
    )
    (net (code "72") (name "unconnected-(A2-GPIO27-Pad36)") (class "Default")
      (node (ref "A2") (pin "36") (pinfunction "GPIO27_36") (pintype "bidirectional"))
    )
    (net (code "73") (name "unconnected-(A2-GPIO28-Pad38)") (class "Default")
      (node (ref "A2") (pin "38") (pinfunction "GPIO28_38") (pintype "bidirectional"))
    )
    (net (code "74") (name "unconnected-(A2-GPIO29-Pad40)") (class "Default")
      (node (ref "A2") (pin "40") (pinfunction "GPIO29_40") (pintype "bidirectional"))
    )
    (net (code "75") (name "unconnected-(A2-ID_SC-Pad28)") (class "Default")
      (node (ref "A2") (pin "28") (pinfunction "ID_SC_28") (pintype "bidirectional"))
    )
    (net (code "76") (name "unconnected-(A2-ID_SD-Pad27)") (class "Default")
      (node (ref "A2") (pin "27") (pinfunction "ID_SD_27") (pintype "bidirectional"))
    )
    (net (code "77") (name "unconnected-(A2-RXD0{slash}GPIO16-Pad10)") (class "Default")
      (node (ref "A2") (pin "10") (pinfunction "RXD0/GPIO16_10") (pintype "bidirectional"))
    )
    (net (code "78") (name "unconnected-(A2-TXD0{slash}GPIO15-Pad8)") (class "Default")
      (node (ref "A2") (pin "8") (pinfunction "TXD0/GPIO15_8") (pintype "bidirectional"))
    )
    (net (code "79") (name "unconnected-(A2-~{CE1}{slash}GPIO11-Pad26)") (class "Default")
      (node (ref "A2") (pin "26") (pinfunction "~{CE1}/GPIO11_26") (pintype "bidirectional"))
    )
    (net (code "80") (name "unconnected-(U2-PGOOD-Pad6)") (class "Default")
      (node (ref "U2") (pin "6") (pinfunction "PGOOD_6") (pintype "output"))
    )
    (net (code "81") (name "unconnected-(U8-*CTS1-Pad24)") (class "Default")
      (node (ref "U8") (pin "24") (pinfunction "*CTS1_24") (pintype "passive"))
    )
    (net (code "82") (name "unconnected-(U8-*CTS2-Pad32)") (class "Default")
      (node (ref "U8") (pin "32") (pinfunction "*CTS2_32") (pintype "passive"))
    )
    (net (code "83") (name "unconnected-(U8-*CTS3-Pad40)") (class "Default")
      (node (ref "U8") (pin "40") (pinfunction "*CTS3_40") (pintype "passive"))
    )
    (net (code "84") (name "unconnected-(U8-XOUT-Pad44)") (class "Default")
      (node (ref "U8") (pin "44") (pinfunction "XOUT_44") (pintype "passive"))
    )
    (net (code "85") (name "unconnected-(Y1-~{ST}-Pad1)") (class "Default")
      (node (ref "Y1") (pin "1") (pinfunction "~{ST}_1") (pintype "input"))
    )
  )
)
